# ArduinoLFO_Output_Board.net
KiCad netlist of a schematic drawn in EAGLE
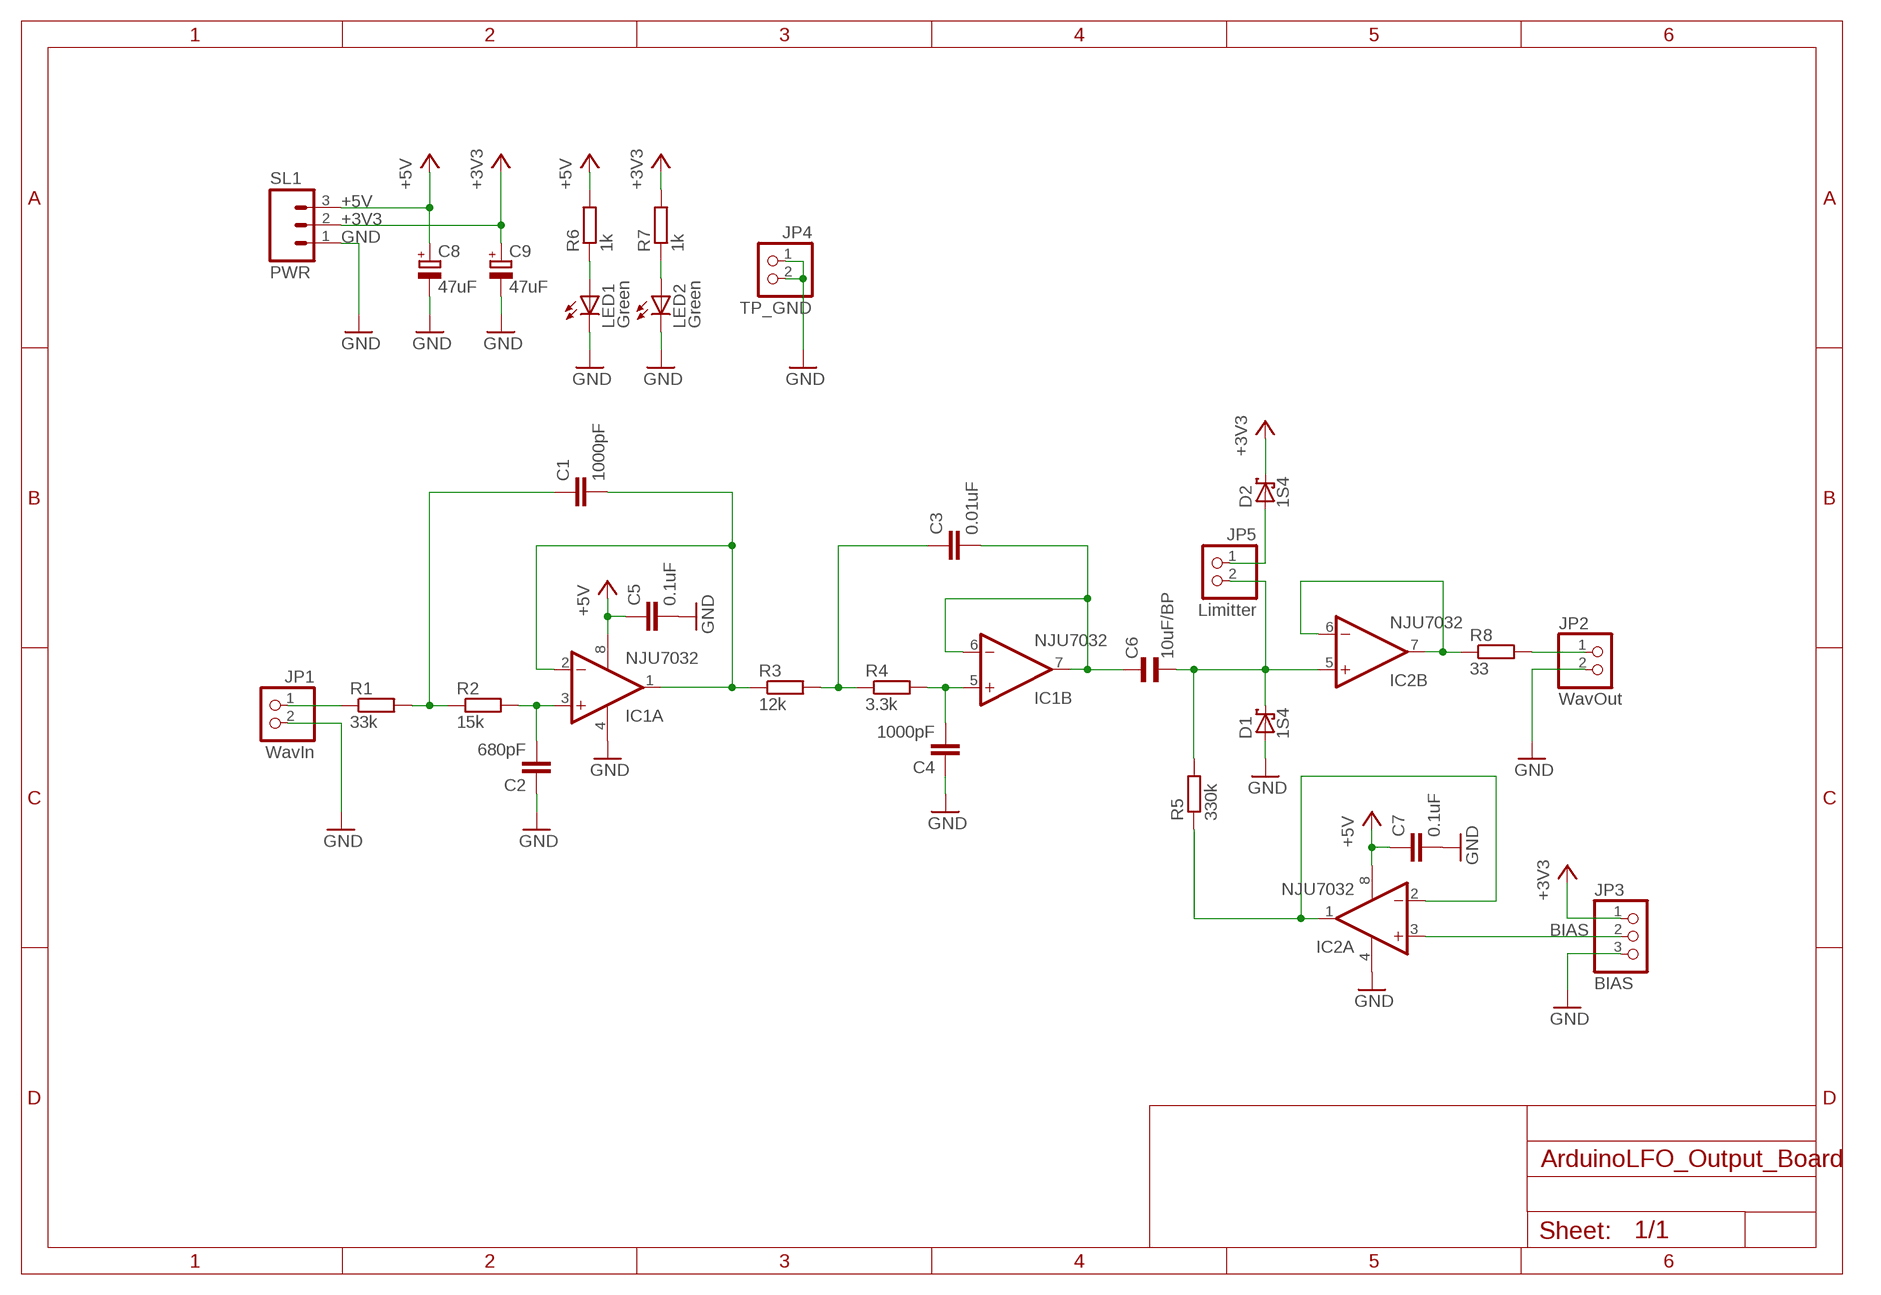
[diagram p0: schematic, sheet 1]

(export (version "E")
  (design (tool "Eeschema 10.0.6"))
  (components
    (comp (ref "C1")
      (value "1000pF")
      (footprint "eagle-import:C050-025X075")
      (libsource (lib "eagle-import") (part "C-EU050-025X075"))
    )
    (comp (ref "C2")
      (value "680pF")
      (footprint "eagle-import:C050-030X075")
      (libsource (lib "eagle-import") (part "C-EU050-030X075"))
    )
    (comp (ref "C3")
      (value "0.01uF")
      (footprint "eagle-import:C050-025X075")
      (libsource (lib "eagle-import") (part "C-EU050-025X075"))
    )
    (comp (ref "C4")
      (value "1000pF")
      (footprint "eagle-import:C050-025X075")
      (libsource (lib "eagle-import") (part "C-EU050-025X075"))
    )
    (comp (ref "C5")
      (value "0.1uF")
      (footprint "eagle-import:C025-024X044")
      (libsource (lib "eagle-import") (part "C-EU025-024X044"))
    )
    (comp (ref "C6")
      (value "10uF/BP")
      (footprint "eagle-import:E5-8,5")
      (libsource (lib "eagle-import") (part "C_BP-E5-8.5"))
    )
    (comp (ref "C7")
      (value "0.1uF")
      (footprint "eagle-import:C025-024X044")
      (libsource (lib "eagle-import") (part "C-EU025-024X044"))
    )
    (comp (ref "C8")
      (value "47uF")
      (footprint "eagle-import:E2,5-6")
      (libsource (lib "eagle-import") (part "CPOL-EUE2.5-6"))
    )
    (comp (ref "C9")
      (value "47uF")
      (footprint "eagle-import:E2,5-6")
      (libsource (lib "eagle-import") (part "CPOL-EUE2.5-6"))
    )
    (comp (ref "D1")
      (value "1S4")
      (footprint "eagle-import:DO35-7")
      (libsource (lib "eagle-import") (part "SCHOTTKY-DIODEDO35-7"))
    )
    (comp (ref "D2")
      (value "1S4")
      (footprint "eagle-import:DO35-7")
      (libsource (lib "eagle-import") (part "SCHOTTKY-DIODEDO35-7"))
    )
    (comp (ref "IC1")
      (value "NJU7032")
      (footprint "eagle-import:DIL08")
      (libsource (lib "eagle-import") (part "LM358N"))
    )
    (comp (ref "IC2")
      (value "NJU7032")
      (footprint "eagle-import:DIL08")
      (libsource (lib "eagle-import") (part "LM358N"))
    )
    (comp (ref "JP1")
      (value "WavIn")
      (footprint "eagle-import:1X02")
      (libsource (lib "eagle-import") (part "PINHD-1X2"))
    )
    (comp (ref "JP2")
      (value "WavOut")
      (footprint "eagle-import:1X02")
      (libsource (lib "eagle-import") (part "PINHD-1X2"))
    )
    (comp (ref "JP3")
      (value "BIAS")
      (footprint "eagle-import:1X03")
      (libsource (lib "eagle-import") (part "PINHD-1X3"))
    )
    (comp (ref "JP4")
      (value "TP_GND")
      (footprint "eagle-import:1X02")
      (libsource (lib "eagle-import") (part "PINHD-1X2"))
    )
    (comp (ref "JP5")
      (value "Limitter")
      (footprint "eagle-import:1X02")
      (libsource (lib "eagle-import") (part "PINHD-1X2"))
    )
    (comp (ref "LED1")
      (value "Green")
      (footprint "eagle-import:LED3MM")
      (libsource (lib "eagle-import") (part "LED3MM"))
    )
    (comp (ref "LED2")
      (value "Green")
      (footprint "eagle-import:LED3MM")
      (libsource (lib "eagle-import") (part "LED3MM"))
    )
    (comp (ref "R1")
      (value "33k")
      (footprint "eagle-import:0207_7")
      (libsource (lib "eagle-import") (part "R-EU_0207/7"))
    )
    (comp (ref "R2")
      (value "15k")
      (footprint "eagle-import:0207_7")
      (libsource (lib "eagle-import") (part "R-EU_0207/7"))
    )
    (comp (ref "R3")
      (value "12k")
      (footprint "eagle-import:0207_7")
      (libsource (lib "eagle-import") (part "R-EU_0207/7"))
    )
    (comp (ref "R4")
      (value "3.3k")
      (footprint "eagle-import:0207_7")
      (libsource (lib "eagle-import") (part "R-EU_0207/7"))
    )
    (comp (ref "R5")
      (value "330k")
      (footprint "eagle-import:0207_7")
      (libsource (lib "eagle-import") (part "R-EU_0207/7"))
    )
    (comp (ref "R6")
      (value "1k")
      (footprint "eagle-import:0207_7")
      (libsource (lib "eagle-import") (part "R-EU_0207/7"))
    )
    (comp (ref "R7")
      (value "1k")
      (footprint "eagle-import:0207_7")
      (libsource (lib "eagle-import") (part "R-EU_0207/7"))
    )
    (comp (ref "R8")
      (value "33")
      (footprint "eagle-import:0207_7")
      (libsource (lib "eagle-import") (part "R-EU_0207/7"))
    )
    (comp (ref "SL1")
      (value "PWR")
      (footprint "eagle-import:03PA")
      (libsource (lib "eagle-import") (part "AMP-EI-M3"))
    )
  )
  (nets
    (net (code "1") (name "+3V3") (class "Default")
      (node (ref "C9") (pin "+") (pinfunction "+_+") (pintype "passive"))
      (node (ref "D2") (pin "C") (pinfunction "C_C") (pintype "passive"))
      (node (ref "JP3") (pin "1") (pinfunction "1_1") (pintype "passive"))
      (node (ref "R7") (pin "2") (pinfunction "2_2") (pintype "passive"))
      (node (ref "SL1") (pin "2") (pinfunction "2_2") (pintype "passive"))
    )
    (net (code "2") (name "+5V") (class "Default")
      (node (ref "C5") (pin "1") (pinfunction "1_1") (pintype "passive"))
      (node (ref "C7") (pin "1") (pinfunction "1_1") (pintype "passive"))
      (node (ref "C8") (pin "+") (pinfunction "+_+") (pintype "passive"))
      (node (ref "IC1") (pin "8") (pinfunction "V+_8") (pintype "power_in"))
      (node (ref "IC2") (pin "8") (pinfunction "V+_8") (pintype "power_in"))
      (node (ref "R6") (pin "2") (pinfunction "2_2") (pintype "passive"))
      (node (ref "SL1") (pin "3") (pinfunction "3_3") (pintype "passive"))
    )
    (net (code "3") (name "/BIAS") (class "Default")
      (node (ref "IC2") (pin "3") (pinfunction "+IN_3") (pintype "input"))
      (node (ref "JP3") (pin "2") (pinfunction "2_2") (pintype "passive"))
    )
    (net (code "4") (name "GND") (class "Default")
      (node (ref "C2") (pin "1") (pinfunction "1_1") (pintype "passive"))
      (node (ref "C4") (pin "1") (pinfunction "1_1") (pintype "passive"))
      (node (ref "C5") (pin "2") (pinfunction "2_2") (pintype "passive"))
      (node (ref "C7") (pin "2") (pinfunction "2_2") (pintype "passive"))
      (node (ref "C8") (pin "-") (pinfunction "-_-") (pintype "passive"))
      (node (ref "C9") (pin "-") (pinfunction "-_-") (pintype "passive"))
      (node (ref "D1") (pin "A") (pinfunction "A_A") (pintype "passive"))
      (node (ref "IC1") (pin "4") (pinfunction "V-_4") (pintype "power_in"))
      (node (ref "IC2") (pin "4") (pinfunction "V-_4") (pintype "power_in"))
      (node (ref "JP1") (pin "2") (pinfunction "2_2") (pintype "passive"))
      (node (ref "JP2") (pin "2") (pinfunction "2_2") (pintype "passive"))
      (node (ref "JP3") (pin "3") (pinfunction "3_3") (pintype "passive"))
      (node (ref "JP4") (pin "1") (pinfunction "1_1") (pintype "passive"))
      (node (ref "JP4") (pin "2") (pinfunction "2_2") (pintype "passive"))
      (node (ref "LED1") (pin "K") (pinfunction "C_K") (pintype "passive"))
      (node (ref "LED2") (pin "K") (pinfunction "C_K") (pintype "passive"))
      (node (ref "SL1") (pin "1") (pinfunction "1_1") (pintype "passive"))
    )
    (net (code "5") (name "Net-(C1-Pad1)") (class "Default")
      (node (ref "C1") (pin "1") (pinfunction "1_1") (pintype "passive"))
      (node (ref "R1") (pin "2") (pinfunction "2_2") (pintype "passive"))
      (node (ref "R2") (pin "1") (pinfunction "1_1") (pintype "passive"))
    )
    (net (code "6") (name "Net-(C3-Pad1)") (class "Default")
      (node (ref "C3") (pin "1") (pinfunction "1_1") (pintype "passive"))
      (node (ref "R3") (pin "2") (pinfunction "2_2") (pintype "passive"))
      (node (ref "R4") (pin "1") (pinfunction "1_1") (pintype "passive"))
    )
    (net (code "7") (name "Net-(D2-PadA)") (class "Default")
      (node (ref "D2") (pin "A") (pinfunction "A_A") (pintype "passive"))
      (node (ref "JP5") (pin "1") (pinfunction "1_1") (pintype "passive"))
    )
    (net (code "8") (name "Net-(IC1A-+IN)") (class "Default")
      (node (ref "C2") (pin "2") (pinfunction "2_2") (pintype "passive"))
      (node (ref "IC1") (pin "3") (pinfunction "+IN_3") (pintype "input"))
      (node (ref "R2") (pin "2") (pinfunction "2_2") (pintype "passive"))
    )
    (net (code "9") (name "Net-(IC1A--IN)") (class "Default")
      (node (ref "C1") (pin "2") (pinfunction "2_2") (pintype "passive"))
      (node (ref "IC1") (pin "1") (pinfunction "OUT_1") (pintype "output"))
      (node (ref "IC1") (pin "2") (pinfunction "-IN_2") (pintype "input"))
      (node (ref "R3") (pin "1") (pinfunction "1_1") (pintype "passive"))
    )
    (net (code "10") (name "Net-(IC1B-+IN)") (class "Default")
      (node (ref "C4") (pin "2") (pinfunction "2_2") (pintype "passive"))
      (node (ref "IC1") (pin "5") (pinfunction "+IN_5") (pintype "input"))
      (node (ref "R4") (pin "2") (pinfunction "2_2") (pintype "passive"))
    )
    (net (code "11") (name "Net-(IC1B--IN)") (class "Default")
      (node (ref "C3") (pin "2") (pinfunction "2_2") (pintype "passive"))
      (node (ref "C6") (pin "1") (pinfunction "1_1") (pintype "passive"))
      (node (ref "IC1") (pin "6") (pinfunction "-IN_6") (pintype "input"))
      (node (ref "IC1") (pin "7") (pinfunction "OUT_7") (pintype "output"))
    )
    (net (code "12") (name "Net-(IC2A--IN)") (class "Default")
      (node (ref "IC2") (pin "1") (pinfunction "OUT_1") (pintype "output"))
      (node (ref "IC2") (pin "2") (pinfunction "-IN_2") (pintype "input"))
      (node (ref "R5") (pin "1") (pinfunction "1_1") (pintype "passive"))
    )
    (net (code "13") (name "Net-(IC2B-+IN)") (class "Default")
      (node (ref "C6") (pin "2") (pinfunction "2_2") (pintype "passive"))
      (node (ref "D1") (pin "C") (pinfunction "C_C") (pintype "passive"))
      (node (ref "IC2") (pin "5") (pinfunction "+IN_5") (pintype "input"))
      (node (ref "JP5") (pin "2") (pinfunction "2_2") (pintype "passive"))
      (node (ref "R5") (pin "2") (pinfunction "2_2") (pintype "passive"))
    )
    (net (code "14") (name "Net-(IC2B--IN)") (class "Default")
      (node (ref "IC2") (pin "6") (pinfunction "-IN_6") (pintype "input"))
      (node (ref "IC2") (pin "7") (pinfunction "OUT_7") (pintype "output"))
      (node (ref "R8") (pin "1") (pinfunction "1_1") (pintype "passive"))
    )
    (net (code "15") (name "Net-(JP1-Pad1)") (class "Default")
      (node (ref "JP1") (pin "1") (pinfunction "1_1") (pintype "passive"))
      (node (ref "R1") (pin "1") (pinfunction "1_1") (pintype "passive"))
    )
    (net (code "16") (name "Net-(JP2-Pad1)") (class "Default")
      (node (ref "JP2") (pin "1") (pinfunction "1_1") (pintype "passive"))
      (node (ref "R8") (pin "2") (pinfunction "2_2") (pintype "passive"))
    )
    (net (code "17") (name "Net-(LED1-PadA)") (class "Default")
      (node (ref "LED1") (pin "A") (pinfunction "A_A") (pintype "passive"))
      (node (ref "R6") (pin "1") (pinfunction "1_1") (pintype "passive"))
    )
    (net (code "18") (name "Net-(LED2-PadA)") (class "Default")
      (node (ref "LED2") (pin "A") (pinfunction "A_A") (pintype "passive"))
      (node (ref "R7") (pin "1") (pinfunction "1_1") (pintype "passive"))
    )
  )
)
